# business_card_serial_conway.net
KiCad netlist of a schematic drawn in EAGLE
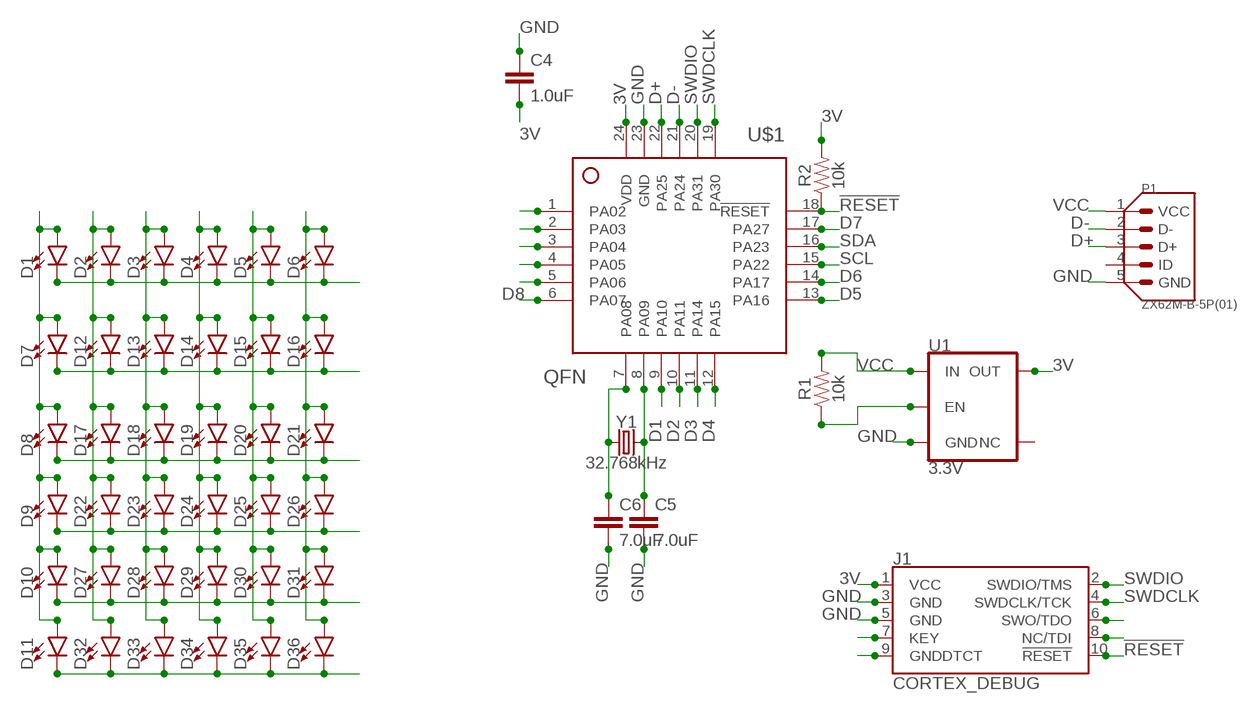
[diagram p0: schematic, sheet 1]

(export (version "E")
  (design (tool "Eeschema 10.0.6"))
  (components
    (comp (ref "C4")
      (value "1.0uF")
      (footprint "eagle-import:0402")
      (libsource (lib "eagle-import") (part "1.0UF-0402-16V-10%"))
    )
    (comp (ref "C5")
      (value "7.0uF")
      (footprint "eagle-import:0402")
      (libsource (lib "eagle-import") (part "1.0UF-0402-16V-10%"))
    )
    (comp (ref "C6")
      (value "7.0uF")
      (footprint "eagle-import:0402")
      (libsource (lib "eagle-import") (part "1.0UF-0402-16V-10%"))
    )
    (comp (ref "D1")
      (value "LED0603")
      (footprint "eagle-import:LED-0603")
      (libsource (lib "eagle-import") (part "LED0603"))
    )
    (comp (ref "D2")
      (value "LED0603")
      (footprint "eagle-import:LED-0603")
      (libsource (lib "eagle-import") (part "LED0603"))
    )
    (comp (ref "D3")
      (value "LED0603")
      (footprint "eagle-import:LED-0603")
      (libsource (lib "eagle-import") (part "LED0603"))
    )
    (comp (ref "D4")
      (value "LED0603")
      (footprint "eagle-import:LED-0603")
      (libsource (lib "eagle-import") (part "LED0603"))
    )
    (comp (ref "D5")
      (value "LED0603")
      (footprint "eagle-import:LED-0603")
      (libsource (lib "eagle-import") (part "LED0603"))
    )
    (comp (ref "D6")
      (value "LED0603")
      (footprint "eagle-import:LED-0603")
      (libsource (lib "eagle-import") (part "LED0603"))
    )
    (comp (ref "D7")
      (value "LED0603")
      (footprint "eagle-import:LED-0603")
      (libsource (lib "eagle-import") (part "LED0603"))
    )
    (comp (ref "D8")
      (value "LED0603")
      (footprint "eagle-import:LED-0603")
      (libsource (lib "eagle-import") (part "LED0603"))
    )
    (comp (ref "D9")
      (value "LED0603")
      (footprint "eagle-import:LED-0603")
      (libsource (lib "eagle-import") (part "LED0603"))
    )
    (comp (ref "D10")
      (value "LED0603")
      (footprint "eagle-import:LED-0603")
      (libsource (lib "eagle-import") (part "LED0603"))
    )
    (comp (ref "D11")
      (value "LED0603")
      (footprint "eagle-import:LED-0603")
      (libsource (lib "eagle-import") (part "LED0603"))
    )
    (comp (ref "D12")
      (value "LED0603")
      (footprint "eagle-import:LED-0603")
      (libsource (lib "eagle-import") (part "LED0603"))
    )
    (comp (ref "D13")
      (value "LED0603")
      (footprint "eagle-import:LED-0603")
      (libsource (lib "eagle-import") (part "LED0603"))
    )
    (comp (ref "D14")
      (value "LED0603")
      (footprint "eagle-import:LED-0603")
      (libsource (lib "eagle-import") (part "LED0603"))
    )
    (comp (ref "D15")
      (value "LED0603")
      (footprint "eagle-import:LED-0603")
      (libsource (lib "eagle-import") (part "LED0603"))
    )
    (comp (ref "D16")
      (value "LED0603")
      (footprint "eagle-import:LED-0603")
      (libsource (lib "eagle-import") (part "LED0603"))
    )
    (comp (ref "D17")
      (value "LED0603")
      (footprint "eagle-import:LED-0603")
      (libsource (lib "eagle-import") (part "LED0603"))
    )
    (comp (ref "D18")
      (value "LED0603")
      (footprint "eagle-import:LED-0603")
      (libsource (lib "eagle-import") (part "LED0603"))
    )
    (comp (ref "D19")
      (value "LED0603")
      (footprint "eagle-import:LED-0603")
      (libsource (lib "eagle-import") (part "LED0603"))
    )
    (comp (ref "D20")
      (value "LED0603")
      (footprint "eagle-import:LED-0603")
      (libsource (lib "eagle-import") (part "LED0603"))
    )
    (comp (ref "D21")
      (value "LED0603")
      (footprint "eagle-import:LED-0603")
      (libsource (lib "eagle-import") (part "LED0603"))
    )
    (comp (ref "D22")
      (value "LED0603")
      (footprint "eagle-import:LED-0603")
      (libsource (lib "eagle-import") (part "LED0603"))
    )
    (comp (ref "D23")
      (value "LED0603")
      (footprint "eagle-import:LED-0603")
      (libsource (lib "eagle-import") (part "LED0603"))
    )
    (comp (ref "D24")
      (value "LED0603")
      (footprint "eagle-import:LED-0603")
      (libsource (lib "eagle-import") (part "LED0603"))
    )
    (comp (ref "D25")
      (value "LED0603")
      (footprint "eagle-import:LED-0603")
      (libsource (lib "eagle-import") (part "LED0603"))
    )
    (comp (ref "D26")
      (value "LED0603")
      (footprint "eagle-import:LED-0603")
      (libsource (lib "eagle-import") (part "LED0603"))
    )
    (comp (ref "D27")
      (value "LED0603")
      (footprint "eagle-import:LED-0603")
      (libsource (lib "eagle-import") (part "LED0603"))
    )
    (comp (ref "D28")
      (value "LED0603")
      (footprint "eagle-import:LED-0603")
      (libsource (lib "eagle-import") (part "LED0603"))
    )
    (comp (ref "D29")
      (value "LED0603")
      (footprint "eagle-import:LED-0603")
      (libsource (lib "eagle-import") (part "LED0603"))
    )
    (comp (ref "D30")
      (value "LED0603")
      (footprint "eagle-import:LED-0603")
      (libsource (lib "eagle-import") (part "LED0603"))
    )
    (comp (ref "D31")
      (value "LED0603")
      (footprint "eagle-import:LED-0603")
      (libsource (lib "eagle-import") (part "LED0603"))
    )
    (comp (ref "D32")
      (value "LED0603")
      (footprint "eagle-import:LED-0603")
      (libsource (lib "eagle-import") (part "LED0603"))
    )
    (comp (ref "D33")
      (value "LED0603")
      (footprint "eagle-import:LED-0603")
      (libsource (lib "eagle-import") (part "LED0603"))
    )
    (comp (ref "D34")
      (value "LED0603")
      (footprint "eagle-import:LED-0603")
      (libsource (lib "eagle-import") (part "LED0603"))
    )
    (comp (ref "D35")
      (value "LED0603")
      (footprint "eagle-import:LED-0603")
      (libsource (lib "eagle-import") (part "LED0603"))
    )
    (comp (ref "D36")
      (value "LED0603")
      (footprint "eagle-import:LED-0603")
      (libsource (lib "eagle-import") (part "LED0603"))
    )
    (comp (ref "J1")
      (value "CORTEX_DEBUG")
      (footprint "eagle-import:2X5-PTH-1.27MM")
      (libsource (lib "eagle-import") (part "CORTEX_DEBUG_PTH"))
    )
    (comp (ref "P1")
      (value "ZX62M-B-5P(01)")
      (footprint "eagle-import:HRS_ZX62M-B-5P(01)")
      (fields (field (name "MF") "Hirose") (field (name "MP") "ZX62M-B-5P_01_"))
      (libsource (lib "eagle-import") (part "ZX62M-B-5P(01)"))
    )
    (comp (ref "R1")
      (value "10k")
      (footprint "eagle-import:0603")
      (libsource (lib "eagle-import") (part "330OHM-0603-1/10W-1%"))
    )
    (comp (ref "R2")
      (value "10k")
      (footprint "eagle-import:0603")
      (libsource (lib "eagle-import") (part "330OHM-0603-1/10W-1%"))
    )
    (comp (ref "U$1")
      (value "QFN")
      (footprint "eagle-import:QFN24-4X4")
      (libsource (lib "eagle-import") (part "QFN"))
    )
    (comp (ref "U1")
      (value "3.3V")
      (footprint "eagle-import:SOT23-5")
      (libsource (lib "eagle-import") (part "V_REG_AP2112K-3.3V"))
    )
    (comp (ref "Y1")
      (value "32.768kHz")
      (footprint "eagle-import:CRYSTAL-SMD-3.2X1.5MM")
      (libsource (lib "eagle-import") (part "CRYSTAL-32.768KHZSMD-3.2X1.5"))
    )
  )
  (nets
    (net (code "1") (name "/3V") (class "Default")
      (node (ref "C4") (pin "2") (pinfunction "2_2") (pintype "passive"))
      (node (ref "J1") (pin "1") (pinfunction "VCC_1") (pintype "bidirectional"))
      (node (ref "R2") (pin "2") (pinfunction "2_2") (pintype "passive"))
      (node (ref "U$1") (pin "24") (pinfunction "VDD_24") (pintype "bidirectional"))
      (node (ref "U1") (pin "5") (pinfunction "OUT_5") (pintype "passive"))
    )
    (net (code "2") (name "/D+") (class "Default")
      (node (ref "P1") (pin "3") (pinfunction "D+_3") (pintype "bidirectional"))
      (node (ref "U$1") (pin "22") (pinfunction "PA25_22") (pintype "bidirectional"))
    )
    (net (code "3") (name "/D-") (class "Default")
      (node (ref "P1") (pin "2") (pinfunction "D-_2") (pintype "bidirectional"))
      (node (ref "U$1") (pin "21") (pinfunction "PA24_21") (pintype "bidirectional"))
    )
    (net (code "4") (name "/D1") (class "Default")
      (node (ref "U$1") (pin "9") (pinfunction "PA10_9") (pintype "bidirectional"))
    )
    (net (code "5") (name "/D2") (class "Default")
      (node (ref "U$1") (pin "10") (pinfunction "PA11_10") (pintype "bidirectional"))
    )
    (net (code "6") (name "/D3") (class "Default")
      (node (ref "U$1") (pin "11") (pinfunction "PA14_11") (pintype "bidirectional"))
    )
    (net (code "7") (name "/D4") (class "Default")
      (node (ref "U$1") (pin "12") (pinfunction "PA15_12") (pintype "bidirectional"))
    )
    (net (code "8") (name "/D5") (class "Default")
      (node (ref "U$1") (pin "13") (pinfunction "PA16_13") (pintype "bidirectional"))
    )
    (net (code "9") (name "/D6") (class "Default")
      (node (ref "U$1") (pin "14") (pinfunction "PA17_14") (pintype "bidirectional"))
    )
    (net (code "10") (name "/D7") (class "Default")
      (node (ref "U$1") (pin "17") (pinfunction "PA27_17") (pintype "bidirectional"))
    )
    (net (code "11") (name "/D8") (class "Default")
      (node (ref "U$1") (pin "6") (pinfunction "PA07_6") (pintype "bidirectional"))
    )
    (net (code "12") (name "/GND") (class "Default")
      (node (ref "C4") (pin "1") (pinfunction "1_1") (pintype "passive"))
      (node (ref "C5") (pin "2") (pinfunction "2_2") (pintype "passive"))
      (node (ref "C6") (pin "2") (pinfunction "2_2") (pintype "passive"))
      (node (ref "J1") (pin "3") (pinfunction "GND_3") (pintype "bidirectional"))
      (node (ref "J1") (pin "5") (pinfunction "GND_5") (pintype "bidirectional"))
      (node (ref "P1") (pin "5") (pinfunction "GND_5") (pintype "passive"))
      (node (ref "U$1") (pin "23") (pinfunction "GND_23") (pintype "bidirectional"))
      (node (ref "U1") (pin "2") (pinfunction "GND_2") (pintype "input"))
    )
    (net (code "13") (name "/SCL") (class "Default")
      (node (ref "U$1") (pin "15") (pinfunction "PA22_15") (pintype "bidirectional"))
    )
    (net (code "14") (name "/SDA") (class "Default")
      (node (ref "U$1") (pin "16") (pinfunction "PA23_16") (pintype "bidirectional"))
    )
    (net (code "15") (name "/SWDCLK") (class "Default")
      (node (ref "J1") (pin "4") (pinfunction "SWDCLK/TCK_4") (pintype "bidirectional"))
      (node (ref "U$1") (pin "19") (pinfunction "PA30_19") (pintype "bidirectional"))
    )
    (net (code "16") (name "/SWDIO") (class "Default")
      (node (ref "J1") (pin "2") (pinfunction "SWDIO/TMS_2") (pintype "bidirectional"))
      (node (ref "U$1") (pin "20") (pinfunction "PA31_20") (pintype "bidirectional"))
    )
    (net (code "17") (name "/VCC") (class "Default")
      (node (ref "P1") (pin "1") (pinfunction "VCC_1") (pintype "power_in"))
      (node (ref "R1") (pin "2") (pinfunction "2_2") (pintype "passive"))
      (node (ref "U1") (pin "1") (pinfunction "IN_1") (pintype "input"))
    )
    (net (code "18") (name "/~{RESET}") (class "Default")
      (node (ref "J1") (pin "10") (pinfunction "~{RESET}_10") (pintype "bidirectional"))
      (node (ref "R2") (pin "1") (pinfunction "1_1") (pintype "passive"))
      (node (ref "U$1") (pin "18") (pinfunction "~{RESET}_18") (pintype "bidirectional"))
    )
    (net (code "19") (name "Net-(D1-PadA)") (class "Default")
      (node (ref "D1") (pin "A") (pinfunction "A_A") (pintype "passive"))
      (node (ref "D10") (pin "A") (pinfunction "A_A") (pintype "passive"))
      (node (ref "D11") (pin "A") (pinfunction "A_A") (pintype "passive"))
      (node (ref "D7") (pin "A") (pinfunction "A_A") (pintype "passive"))
      (node (ref "D8") (pin "A") (pinfunction "A_A") (pintype "passive"))
      (node (ref "D9") (pin "A") (pinfunction "A_A") (pintype "passive"))
    )
    (net (code "20") (name "Net-(D1-PadC)") (class "Default")
      (node (ref "D1") (pin "C") (pinfunction "C_C") (pintype "passive"))
      (node (ref "D2") (pin "C") (pinfunction "C_C") (pintype "passive"))
      (node (ref "D3") (pin "C") (pinfunction "C_C") (pintype "passive"))
      (node (ref "D4") (pin "C") (pinfunction "C_C") (pintype "passive"))
      (node (ref "D5") (pin "C") (pinfunction "C_C") (pintype "passive"))
      (node (ref "D6") (pin "C") (pinfunction "C_C") (pintype "passive"))
    )
    (net (code "21") (name "Net-(D10-PadC)") (class "Default")
      (node (ref "D10") (pin "C") (pinfunction "C_C") (pintype "passive"))
      (node (ref "D27") (pin "C") (pinfunction "C_C") (pintype "passive"))
      (node (ref "D28") (pin "C") (pinfunction "C_C") (pintype "passive"))
      (node (ref "D29") (pin "C") (pinfunction "C_C") (pintype "passive"))
      (node (ref "D30") (pin "C") (pinfunction "C_C") (pintype "passive"))
      (node (ref "D31") (pin "C") (pinfunction "C_C") (pintype "passive"))
    )
    (net (code "22") (name "Net-(D11-PadC)") (class "Default")
      (node (ref "D11") (pin "C") (pinfunction "C_C") (pintype "passive"))
      (node (ref "D32") (pin "C") (pinfunction "C_C") (pintype "passive"))
      (node (ref "D33") (pin "C") (pinfunction "C_C") (pintype "passive"))
      (node (ref "D34") (pin "C") (pinfunction "C_C") (pintype "passive"))
      (node (ref "D35") (pin "C") (pinfunction "C_C") (pintype "passive"))
      (node (ref "D36") (pin "C") (pinfunction "C_C") (pintype "passive"))
    )
    (net (code "23") (name "Net-(D12-PadA)") (class "Default")
      (node (ref "D12") (pin "A") (pinfunction "A_A") (pintype "passive"))
      (node (ref "D17") (pin "A") (pinfunction "A_A") (pintype "passive"))
      (node (ref "D2") (pin "A") (pinfunction "A_A") (pintype "passive"))
      (node (ref "D22") (pin "A") (pinfunction "A_A") (pintype "passive"))
      (node (ref "D27") (pin "A") (pinfunction "A_A") (pintype "passive"))
      (node (ref "D32") (pin "A") (pinfunction "A_A") (pintype "passive"))
    )
    (net (code "24") (name "Net-(D12-PadC)") (class "Default")
      (node (ref "D12") (pin "C") (pinfunction "C_C") (pintype "passive"))
      (node (ref "D13") (pin "C") (pinfunction "C_C") (pintype "passive"))
      (node (ref "D14") (pin "C") (pinfunction "C_C") (pintype "passive"))
      (node (ref "D15") (pin "C") (pinfunction "C_C") (pintype "passive"))
      (node (ref "D16") (pin "C") (pinfunction "C_C") (pintype "passive"))
      (node (ref "D7") (pin "C") (pinfunction "C_C") (pintype "passive"))
    )
    (net (code "25") (name "Net-(D13-PadA)") (class "Default")
      (node (ref "D13") (pin "A") (pinfunction "A_A") (pintype "passive"))
      (node (ref "D18") (pin "A") (pinfunction "A_A") (pintype "passive"))
      (node (ref "D23") (pin "A") (pinfunction "A_A") (pintype "passive"))
      (node (ref "D28") (pin "A") (pinfunction "A_A") (pintype "passive"))
      (node (ref "D3") (pin "A") (pinfunction "A_A") (pintype "passive"))
      (node (ref "D33") (pin "A") (pinfunction "A_A") (pintype "passive"))
    )
    (net (code "26") (name "Net-(D14-PadA)") (class "Default")
      (node (ref "D14") (pin "A") (pinfunction "A_A") (pintype "passive"))
      (node (ref "D19") (pin "A") (pinfunction "A_A") (pintype "passive"))
      (node (ref "D24") (pin "A") (pinfunction "A_A") (pintype "passive"))
      (node (ref "D29") (pin "A") (pinfunction "A_A") (pintype "passive"))
      (node (ref "D34") (pin "A") (pinfunction "A_A") (pintype "passive"))
      (node (ref "D4") (pin "A") (pinfunction "A_A") (pintype "passive"))
    )
    (net (code "27") (name "Net-(D15-PadA)") (class "Default")
      (node (ref "D15") (pin "A") (pinfunction "A_A") (pintype "passive"))
      (node (ref "D20") (pin "A") (pinfunction "A_A") (pintype "passive"))
      (node (ref "D25") (pin "A") (pinfunction "A_A") (pintype "passive"))
      (node (ref "D30") (pin "A") (pinfunction "A_A") (pintype "passive"))
      (node (ref "D35") (pin "A") (pinfunction "A_A") (pintype "passive"))
      (node (ref "D5") (pin "A") (pinfunction "A_A") (pintype "passive"))
    )
    (net (code "28") (name "Net-(D16-PadA)") (class "Default")
      (node (ref "D16") (pin "A") (pinfunction "A_A") (pintype "passive"))
      (node (ref "D21") (pin "A") (pinfunction "A_A") (pintype "passive"))
      (node (ref "D26") (pin "A") (pinfunction "A_A") (pintype "passive"))
      (node (ref "D31") (pin "A") (pinfunction "A_A") (pintype "passive"))
      (node (ref "D36") (pin "A") (pinfunction "A_A") (pintype "passive"))
      (node (ref "D6") (pin "A") (pinfunction "A_A") (pintype "passive"))
    )
    (net (code "29") (name "Net-(D17-PadC)") (class "Default")
      (node (ref "D17") (pin "C") (pinfunction "C_C") (pintype "passive"))
      (node (ref "D18") (pin "C") (pinfunction "C_C") (pintype "passive"))
      (node (ref "D19") (pin "C") (pinfunction "C_C") (pintype "passive"))
      (node (ref "D20") (pin "C") (pinfunction "C_C") (pintype "passive"))
      (node (ref "D21") (pin "C") (pinfunction "C_C") (pintype "passive"))
      (node (ref "D8") (pin "C") (pinfunction "C_C") (pintype "passive"))
    )
    (net (code "30") (name "Net-(D22-PadC)") (class "Default")
      (node (ref "D22") (pin "C") (pinfunction "C_C") (pintype "passive"))
      (node (ref "D23") (pin "C") (pinfunction "C_C") (pintype "passive"))
      (node (ref "D24") (pin "C") (pinfunction "C_C") (pintype "passive"))
      (node (ref "D25") (pin "C") (pinfunction "C_C") (pintype "passive"))
      (node (ref "D26") (pin "C") (pinfunction "C_C") (pintype "passive"))
      (node (ref "D9") (pin "C") (pinfunction "C_C") (pintype "passive"))
    )
    (net (code "31") (name "Net-(U$1-PA08)") (class "Default")
      (node (ref "C6") (pin "1") (pinfunction "1_1") (pintype "passive"))
      (node (ref "U$1") (pin "7") (pinfunction "PA08_7") (pintype "bidirectional"))
      (node (ref "Y1") (pin "P$1") (pinfunction "1_P$1") (pintype "passive"))
    )
    (net (code "32") (name "Net-(U$1-PA09)") (class "Default")
      (node (ref "C5") (pin "1") (pinfunction "1_1") (pintype "passive"))
      (node (ref "U$1") (pin "8") (pinfunction "PA09_8") (pintype "bidirectional"))
      (node (ref "Y1") (pin "P$2") (pinfunction "2_P$2") (pintype "passive"))
    )
    (net (code "33") (name "Net-(U1-EN)") (class "Default")
      (node (ref "R1") (pin "1") (pinfunction "1_1") (pintype "passive"))
      (node (ref "U1") (pin "3") (pinfunction "EN_3") (pintype "input"))
    )
    (net (code "34") (name "unconnected-(J1-GNDDTCT-Pad9)") (class "Default")
      (node (ref "J1") (pin "9") (pinfunction "GNDDTCT_9") (pintype "bidirectional"))
    )
    (net (code "35") (name "unconnected-(J1-KEY-Pad7)") (class "Default")
      (node (ref "J1") (pin "7") (pinfunction "KEY_7") (pintype "bidirectional"))
    )
    (net (code "36") (name "unconnected-(J1-NC{slash}TDI-Pad8)") (class "Default")
      (node (ref "J1") (pin "8") (pinfunction "NC/TDI_8") (pintype "bidirectional"))
    )
    (net (code "37") (name "unconnected-(J1-SWO{slash}TDO-Pad6)") (class "Default")
      (node (ref "J1") (pin "6") (pinfunction "SWO/TDO_6") (pintype "bidirectional"))
    )
    (net (code "38") (name "unconnected-(P1-ID-Pad4)") (class "Default")
      (node (ref "P1") (pin "4") (pinfunction "ID_4") (pintype "bidirectional"))
    )
    (net (code "39") (name "unconnected-(U$1-PA02-Pad1)") (class "Default")
      (node (ref "U$1") (pin "1") (pinfunction "PA02_1") (pintype "bidirectional"))
    )
    (net (code "40") (name "unconnected-(U$1-PA03-Pad2)") (class "Default")
      (node (ref "U$1") (pin "2") (pinfunction "PA03_2") (pintype "bidirectional"))
    )
    (net (code "41") (name "unconnected-(U$1-PA04-Pad3)") (class "Default")
      (node (ref "U$1") (pin "3") (pinfunction "PA04_3") (pintype "bidirectional"))
    )
    (net (code "42") (name "unconnected-(U$1-PA05-Pad4)") (class "Default")
      (node (ref "U$1") (pin "4") (pinfunction "PA05_4") (pintype "bidirectional"))
    )
    (net (code "43") (name "unconnected-(U$1-PA06-Pad5)") (class "Default")
      (node (ref "U$1") (pin "5") (pinfunction "PA06_5") (pintype "bidirectional"))
    )
    (net (code "44") (name "unconnected-(U1-NC-Pad4)") (class "Default")
      (node (ref "U1") (pin "4") (pinfunction "NC_4") (pintype "no_connect"))
    )
  )
)
